# UPbrdEDP.net
KiCad netlist of a schematic drawn in EAGLE
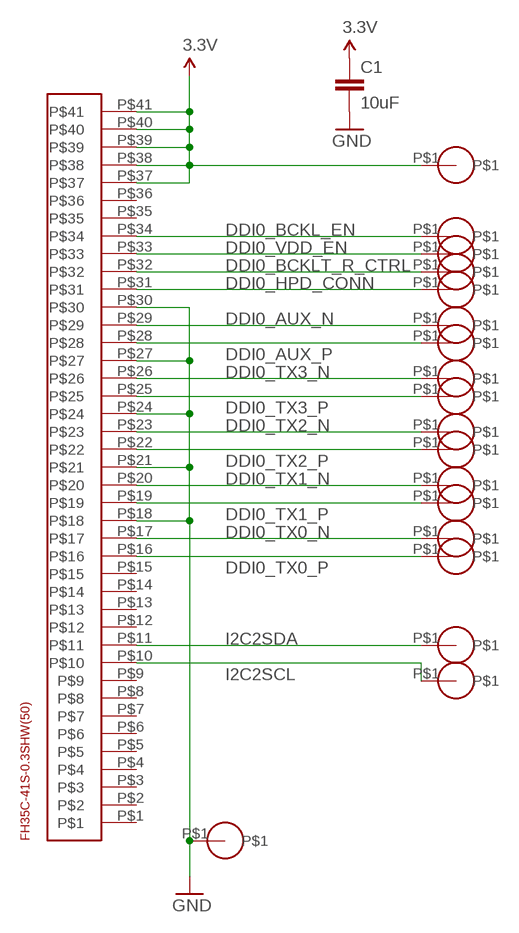
[diagram p0: schematic, sheet 1]

(export (version "E")
  (design (tool "Eeschema 10.0.6"))
  (components
    (comp (ref "C1")
      (value "10uF")
      (footprint "eagle-import:0603-CAP")
      (libsource (lib "eagle-import") (part "10UF-6.3V-20%(0603)"))
    )
    (comp (ref "U$1")
      (value "FH35C-41S-0.3SHW(50)")
      (footprint "eagle-import:FH35C-41S-0.3SHW(50)")
      (libsource (lib "eagle-import") (part "FH35C-41S-0.3SHW(50)"))
    )
    (comp (ref "U$2")
      (value "SOLDERPAD")
      (footprint "eagle-import:SOLDERPAD")
      (libsource (lib "eagle-import") (part "SOLDERPAD"))
    )
    (comp (ref "U$3")
      (value "SOLDERPAD")
      (footprint "eagle-import:SOLDERPAD")
      (libsource (lib "eagle-import") (part "SOLDERPAD"))
    )
    (comp (ref "U$4")
      (value "SOLDERPAD")
      (footprint "eagle-import:SOLDERPAD")
      (libsource (lib "eagle-import") (part "SOLDERPAD"))
    )
    (comp (ref "U$5")
      (value "SOLDERPAD")
      (footprint "eagle-import:SOLDERPAD")
      (libsource (lib "eagle-import") (part "SOLDERPAD"))
    )
    (comp (ref "U$6")
      (value "SOLDERPAD")
      (footprint "eagle-import:SOLDERPAD")
      (libsource (lib "eagle-import") (part "SOLDERPAD"))
    )
    (comp (ref "U$7")
      (value "SOLDERPAD")
      (footprint "eagle-import:SOLDERPAD")
      (libsource (lib "eagle-import") (part "SOLDERPAD"))
    )
    (comp (ref "U$8")
      (value "SOLDERPAD")
      (footprint "eagle-import:SOLDERPAD")
      (libsource (lib "eagle-import") (part "SOLDERPAD"))
    )
    (comp (ref "U$9")
      (value "SOLDERPAD")
      (footprint "eagle-import:SOLDERPAD")
      (libsource (lib "eagle-import") (part "SOLDERPAD"))
    )
    (comp (ref "U$10")
      (value "SOLDERPAD")
      (footprint "eagle-import:SOLDERPAD")
      (libsource (lib "eagle-import") (part "SOLDERPAD"))
    )
    (comp (ref "U$11")
      (value "SOLDERPAD")
      (footprint "eagle-import:SOLDERPAD")
      (libsource (lib "eagle-import") (part "SOLDERPAD"))
    )
    (comp (ref "U$12")
      (value "SOLDERPAD")
      (footprint "eagle-import:SOLDERPAD")
      (libsource (lib "eagle-import") (part "SOLDERPAD"))
    )
    (comp (ref "U$13")
      (value "SOLDERPAD")
      (footprint "eagle-import:SOLDERPAD")
      (libsource (lib "eagle-import") (part "SOLDERPAD"))
    )
    (comp (ref "U$14")
      (value "SOLDERPAD")
      (footprint "eagle-import:SOLDERPAD")
      (libsource (lib "eagle-import") (part "SOLDERPAD"))
    )
    (comp (ref "U$15")
      (value "SOLDERPAD")
      (footprint "eagle-import:SOLDERPAD")
      (libsource (lib "eagle-import") (part "SOLDERPAD"))
    )
    (comp (ref "U$16")
      (value "SOLDERPAD")
      (footprint "eagle-import:SOLDERPAD")
      (libsource (lib "eagle-import") (part "SOLDERPAD"))
    )
    (comp (ref "U$17")
      (value "SOLDERPAD")
      (footprint "eagle-import:SOLDERPAD")
      (libsource (lib "eagle-import") (part "SOLDERPAD"))
    )
    (comp (ref "U$18")
      (value "SOLDERPAD")
      (footprint "eagle-import:SOLDERPAD")
      (libsource (lib "eagle-import") (part "SOLDERPAD"))
    )
    (comp (ref "U$19")
      (value "SOLDERPAD")
      (footprint "eagle-import:SOLDERPAD")
      (libsource (lib "eagle-import") (part "SOLDERPAD"))
    )
  )
  (nets
    (net (code "1") (name "/DDI0_AUX_N") (class "Default")
      (node (ref "U$1") (pin "P$29") (pinfunction "P$29_P$29") (pintype "bidirectional"))
      (node (ref "U$13") (pin "P$1") (pinfunction "P$1_P$1") (pintype "bidirectional"))
    )
    (net (code "2") (name "/DDI0_AUX_P") (class "Default")
      (node (ref "U$1") (pin "P$28") (pinfunction "P$28_P$28") (pintype "bidirectional"))
      (node (ref "U$12") (pin "P$1") (pinfunction "P$1_P$1") (pintype "bidirectional"))
    )
    (net (code "3") (name "/DDI0_BCKLT_R_CTRL") (class "Default")
      (node (ref "U$1") (pin "P$32") (pinfunction "P$32_P$32") (pintype "bidirectional"))
      (node (ref "U$15") (pin "P$1") (pinfunction "P$1_P$1") (pintype "bidirectional"))
    )
    (net (code "4") (name "/DDI0_BCKL_EN") (class "Default")
      (node (ref "U$1") (pin "P$34") (pinfunction "P$34_P$34") (pintype "bidirectional"))
      (node (ref "U$17") (pin "P$1") (pinfunction "P$1_P$1") (pintype "bidirectional"))
    )
    (net (code "5") (name "/DDI0_HPD_CONN") (class "Default")
      (node (ref "U$1") (pin "P$31") (pinfunction "P$31_P$31") (pintype "bidirectional"))
      (node (ref "U$14") (pin "P$1") (pinfunction "P$1_P$1") (pintype "bidirectional"))
    )
    (net (code "6") (name "/DDI0_TX0_N") (class "Default")
      (node (ref "U$1") (pin "P$17") (pinfunction "P$17_P$17") (pintype "bidirectional"))
      (node (ref "U$5") (pin "P$1") (pinfunction "P$1_P$1") (pintype "bidirectional"))
    )
    (net (code "7") (name "/DDI0_TX0_P") (class "Default")
      (node (ref "U$1") (pin "P$16") (pinfunction "P$16_P$16") (pintype "bidirectional"))
      (node (ref "U$4") (pin "P$1") (pinfunction "P$1_P$1") (pintype "bidirectional"))
    )
    (net (code "8") (name "/DDI0_TX1_N") (class "Default")
      (node (ref "U$1") (pin "P$20") (pinfunction "P$20_P$20") (pintype "bidirectional"))
      (node (ref "U$7") (pin "P$1") (pinfunction "P$1_P$1") (pintype "bidirectional"))
    )
    (net (code "9") (name "/DDI0_TX1_P") (class "Default")
      (node (ref "U$1") (pin "P$19") (pinfunction "P$19_P$19") (pintype "bidirectional"))
      (node (ref "U$6") (pin "P$1") (pinfunction "P$1_P$1") (pintype "bidirectional"))
    )
    (net (code "10") (name "/DDI0_TX2_N") (class "Default")
      (node (ref "U$1") (pin "P$23") (pinfunction "P$23_P$23") (pintype "bidirectional"))
      (node (ref "U$9") (pin "P$1") (pinfunction "P$1_P$1") (pintype "bidirectional"))
    )
    (net (code "11") (name "/DDI0_TX2_P") (class "Default")
      (node (ref "U$1") (pin "P$22") (pinfunction "P$22_P$22") (pintype "bidirectional"))
      (node (ref "U$8") (pin "P$1") (pinfunction "P$1_P$1") (pintype "bidirectional"))
    )
    (net (code "12") (name "/DDI0_TX3_N") (class "Default")
      (node (ref "U$1") (pin "P$26") (pinfunction "P$26_P$26") (pintype "bidirectional"))
      (node (ref "U$11") (pin "P$1") (pinfunction "P$1_P$1") (pintype "bidirectional"))
    )
    (net (code "13") (name "/DDI0_TX3_P") (class "Default")
      (node (ref "U$1") (pin "P$25") (pinfunction "P$25_P$25") (pintype "bidirectional"))
      (node (ref "U$10") (pin "P$1") (pinfunction "P$1_P$1") (pintype "bidirectional"))
    )
    (net (code "14") (name "/DDI0_VDD_EN") (class "Default")
      (node (ref "U$1") (pin "P$33") (pinfunction "P$33_P$33") (pintype "bidirectional"))
      (node (ref "U$16") (pin "P$1") (pinfunction "P$1_P$1") (pintype "bidirectional"))
    )
    (net (code "15") (name "/I2C2SCL") (class "Default")
      (node (ref "U$1") (pin "P$10") (pinfunction "P$10_P$10") (pintype "bidirectional"))
      (node (ref "U$3") (pin "P$1") (pinfunction "P$1_P$1") (pintype "bidirectional"))
    )
    (net (code "16") (name "/I2C2SDA") (class "Default")
      (node (ref "U$1") (pin "P$11") (pinfunction "P$11_P$11") (pintype "bidirectional"))
      (node (ref "U$2") (pin "P$1") (pinfunction "P$1_P$1") (pintype "bidirectional"))
    )
    (net (code "17") (name "3.3V") (class "Default")
      (node (ref "C1") (pin "1") (pinfunction "1_1") (pintype "passive"))
      (node (ref "U$1") (pin "P$37") (pinfunction "P$37_P$37") (pintype "bidirectional"))
      (node (ref "U$1") (pin "P$38") (pinfunction "P$38_P$38") (pintype "bidirectional"))
      (node (ref "U$1") (pin "P$39") (pinfunction "P$39_P$39") (pintype "bidirectional"))
      (node (ref "U$1") (pin "P$40") (pinfunction "P$40_P$40") (pintype "bidirectional"))
      (node (ref "U$1") (pin "P$41") (pinfunction "P$41_P$41") (pintype "bidirectional"))
      (node (ref "U$18") (pin "P$1") (pinfunction "P$1_P$1") (pintype "bidirectional"))
    )
    (net (code "18") (name "GND") (class "Default")
      (node (ref "C1") (pin "2") (pinfunction "2_2") (pintype "passive"))
      (node (ref "U$1") (pin "P$18") (pinfunction "P$18_P$18") (pintype "bidirectional"))
      (node (ref "U$1") (pin "P$21") (pinfunction "P$21_P$21") (pintype "bidirectional"))
      (node (ref "U$1") (pin "P$24") (pinfunction "P$24_P$24") (pintype "bidirectional"))
      (node (ref "U$1") (pin "P$27") (pinfunction "P$27_P$27") (pintype "bidirectional"))
      (node (ref "U$1") (pin "P$30") (pinfunction "P$30_P$30") (pintype "bidirectional"))
      (node (ref "U$19") (pin "P$1") (pinfunction "P$1_P$1") (pintype "bidirectional"))
    )
    (net (code "19") (name "unconnected-(U$1-PadP$1)") (class "Default")
      (node (ref "U$1") (pin "P$1") (pinfunction "P$1_P$1") (pintype "bidirectional"))
    )
    (net (code "20") (name "unconnected-(U$1-PadP$2)") (class "Default")
      (node (ref "U$1") (pin "P$2") (pinfunction "P$2_P$2") (pintype "bidirectional"))
    )
    (net (code "21") (name "unconnected-(U$1-PadP$3)") (class "Default")
      (node (ref "U$1") (pin "P$3") (pinfunction "P$3_P$3") (pintype "bidirectional"))
    )
    (net (code "22") (name "unconnected-(U$1-PadP$4)") (class "Default")
      (node (ref "U$1") (pin "P$4") (pinfunction "P$4_P$4") (pintype "bidirectional"))
    )
    (net (code "23") (name "unconnected-(U$1-PadP$5)") (class "Default")
      (node (ref "U$1") (pin "P$5") (pinfunction "P$5_P$5") (pintype "bidirectional"))
    )
    (net (code "24") (name "unconnected-(U$1-PadP$6)") (class "Default")
      (node (ref "U$1") (pin "P$6") (pinfunction "P$6_P$6") (pintype "bidirectional"))
    )
    (net (code "25") (name "unconnected-(U$1-PadP$7)") (class "Default")
      (node (ref "U$1") (pin "P$7") (pinfunction "P$7_P$7") (pintype "bidirectional"))
    )
    (net (code "26") (name "unconnected-(U$1-PadP$8)") (class "Default")
      (node (ref "U$1") (pin "P$8") (pinfunction "P$8_P$8") (pintype "bidirectional"))
    )
    (net (code "27") (name "unconnected-(U$1-PadP$9)") (class "Default")
      (node (ref "U$1") (pin "P$9") (pinfunction "P$9_P$9") (pintype "bidirectional"))
    )
    (net (code "28") (name "unconnected-(U$1-PadP$12)") (class "Default")
      (node (ref "U$1") (pin "P$12") (pinfunction "P$12_P$12") (pintype "bidirectional"))
    )
    (net (code "29") (name "unconnected-(U$1-PadP$13)") (class "Default")
      (node (ref "U$1") (pin "P$13") (pinfunction "P$13_P$13") (pintype "bidirectional"))
    )
    (net (code "30") (name "unconnected-(U$1-PadP$14)") (class "Default")
      (node (ref "U$1") (pin "P$14") (pinfunction "P$14_P$14") (pintype "bidirectional"))
    )
    (net (code "31") (name "unconnected-(U$1-PadP$15)") (class "Default")
      (node (ref "U$1") (pin "P$15") (pinfunction "P$15_P$15") (pintype "bidirectional"))
    )
    (net (code "32") (name "unconnected-(U$1-PadP$35)") (class "Default")
      (node (ref "U$1") (pin "P$35") (pinfunction "P$35_P$35") (pintype "bidirectional"))
    )
    (net (code "33") (name "unconnected-(U$1-PadP$36)") (class "Default")
      (node (ref "U$1") (pin "P$36") (pinfunction "P$36_P$36") (pintype "bidirectional"))
    )
  )
)
